# 2017_MADS.net
KiCad netlist of a schematic drawn in Altium Designer
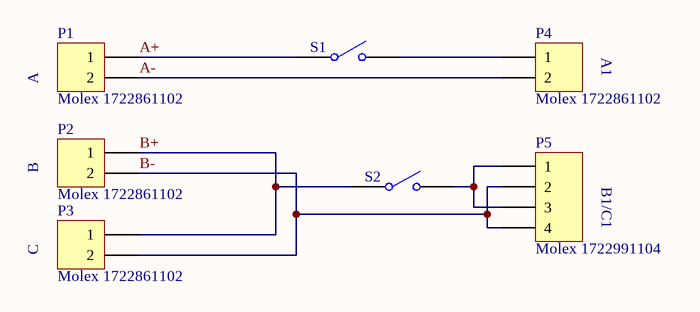
[diagram p0: 2017_MADS.SchDoc]

(export (version "E")
  (design (tool "Eeschema 10.0.6"))
  (components
    (comp (ref "P1")
      (value "Molex 1722861102")
      (footprint "Molex 1722861102")
      (description "ULTRAFIT CONN HDR 02CKT")
      (libsource (lib "2017_MADS") (part "Molex 1722861102"))
    )
    (comp (ref "P2")
      (value "Molex 1722861102")
      (footprint "Molex 1722861102")
      (description "ULTRAFIT CONN HDR 02CKT")
      (libsource (lib "2017_MADS") (part "Molex 1722861102"))
    )
    (comp (ref "P3")
      (value "Molex 1722861102")
      (footprint "Molex 1722861102")
      (description "ULTRAFIT CONN HDR 02CKT")
      (libsource (lib "2017_MADS") (part "Molex 1722861102"))
    )
    (comp (ref "P4")
      (value "Molex 1722861102")
      (footprint "Molex 1722861102")
      (description "ULTRAFIT CONN HDR 02CKT")
      (libsource (lib "") (part "Molex 1722861102_1"))
    )
    (comp (ref "P5")
      (value "Molex 1722991104")
      (footprint "Molex 1722991104")
      (description "ULTRAFIT VERT TIN PLATED BLK")
      (libsource (lib "2017_MADS") (part "Molex 1722991104"))
    )
    (comp (ref "S1")
      (value "SW-SPST")
      (footprint "Screw Switch")
      (description "Single-Pole, Single-Throw Switch")
      (fields (field (name "PUBLISHER") "Altium Limited"))
      (libsource (lib "Miscellaneous Devices") (part "SW-SPST"))
    )
    (comp (ref "S2")
      (value "SW-SPST")
      (footprint "Screw Switch")
      (description "Single-Pole, Single-Throw Switch")
      (fields (field (name "PUBLISHER") "Altium Limited"))
      (libsource (lib "Miscellaneous Devices") (part "SW-SPST"))
    )
  )
  (nets
    (net (code "1") (name "/A+") (class "Default")
      (node (ref "P1") (pin "1") (pinfunction "1_1") (pintype "passive"))
      (node (ref "S1") (pin "1") (pinfunction "COMMON_1") (pintype "passive"))
    )
    (net (code "2") (name "/A-") (class "Default")
      (node (ref "P1") (pin "2") (pinfunction "2_2") (pintype "passive"))
      (node (ref "P4") (pin "2") (pinfunction "2_2") (pintype "passive"))
    )
    (net (code "3") (name "/B+") (class "Default")
      (node (ref "P2") (pin "1") (pinfunction "1_1") (pintype "passive"))
      (node (ref "P3") (pin "1") (pinfunction "1_1") (pintype "passive"))
      (node (ref "S2") (pin "1") (pinfunction "COMMON_1") (pintype "passive"))
    )
    (net (code "4") (name "/B-") (class "Default")
      (node (ref "P2") (pin "2") (pinfunction "2_2") (pintype "passive"))
      (node (ref "P3") (pin "2") (pinfunction "2_2") (pintype "passive"))
      (node (ref "P5") (pin "2") (pinfunction "2_2") (pintype "passive"))
      (node (ref "P5") (pin "4") (pinfunction "4_4") (pintype "passive"))
    )
    (net (code "5") (name "Net-(S1-NO)") (class "Default")
      (node (ref "P4") (pin "1") (pinfunction "1_1") (pintype "passive"))
      (node (ref "S1") (pin "2") (pinfunction "NO_2") (pintype "passive"))
    )
    (net (code "6") (name "Net-(S2-NO)") (class "Default")
      (node (ref "P5") (pin "1") (pinfunction "1_1") (pintype "passive"))
      (node (ref "P5") (pin "3") (pinfunction "3_3") (pintype "passive"))
      (node (ref "S2") (pin "2") (pinfunction "NO_2") (pintype "passive"))
    )
  )
)
